# Board1a.net
KiCad netlist of a schematic drawn in EAGLE
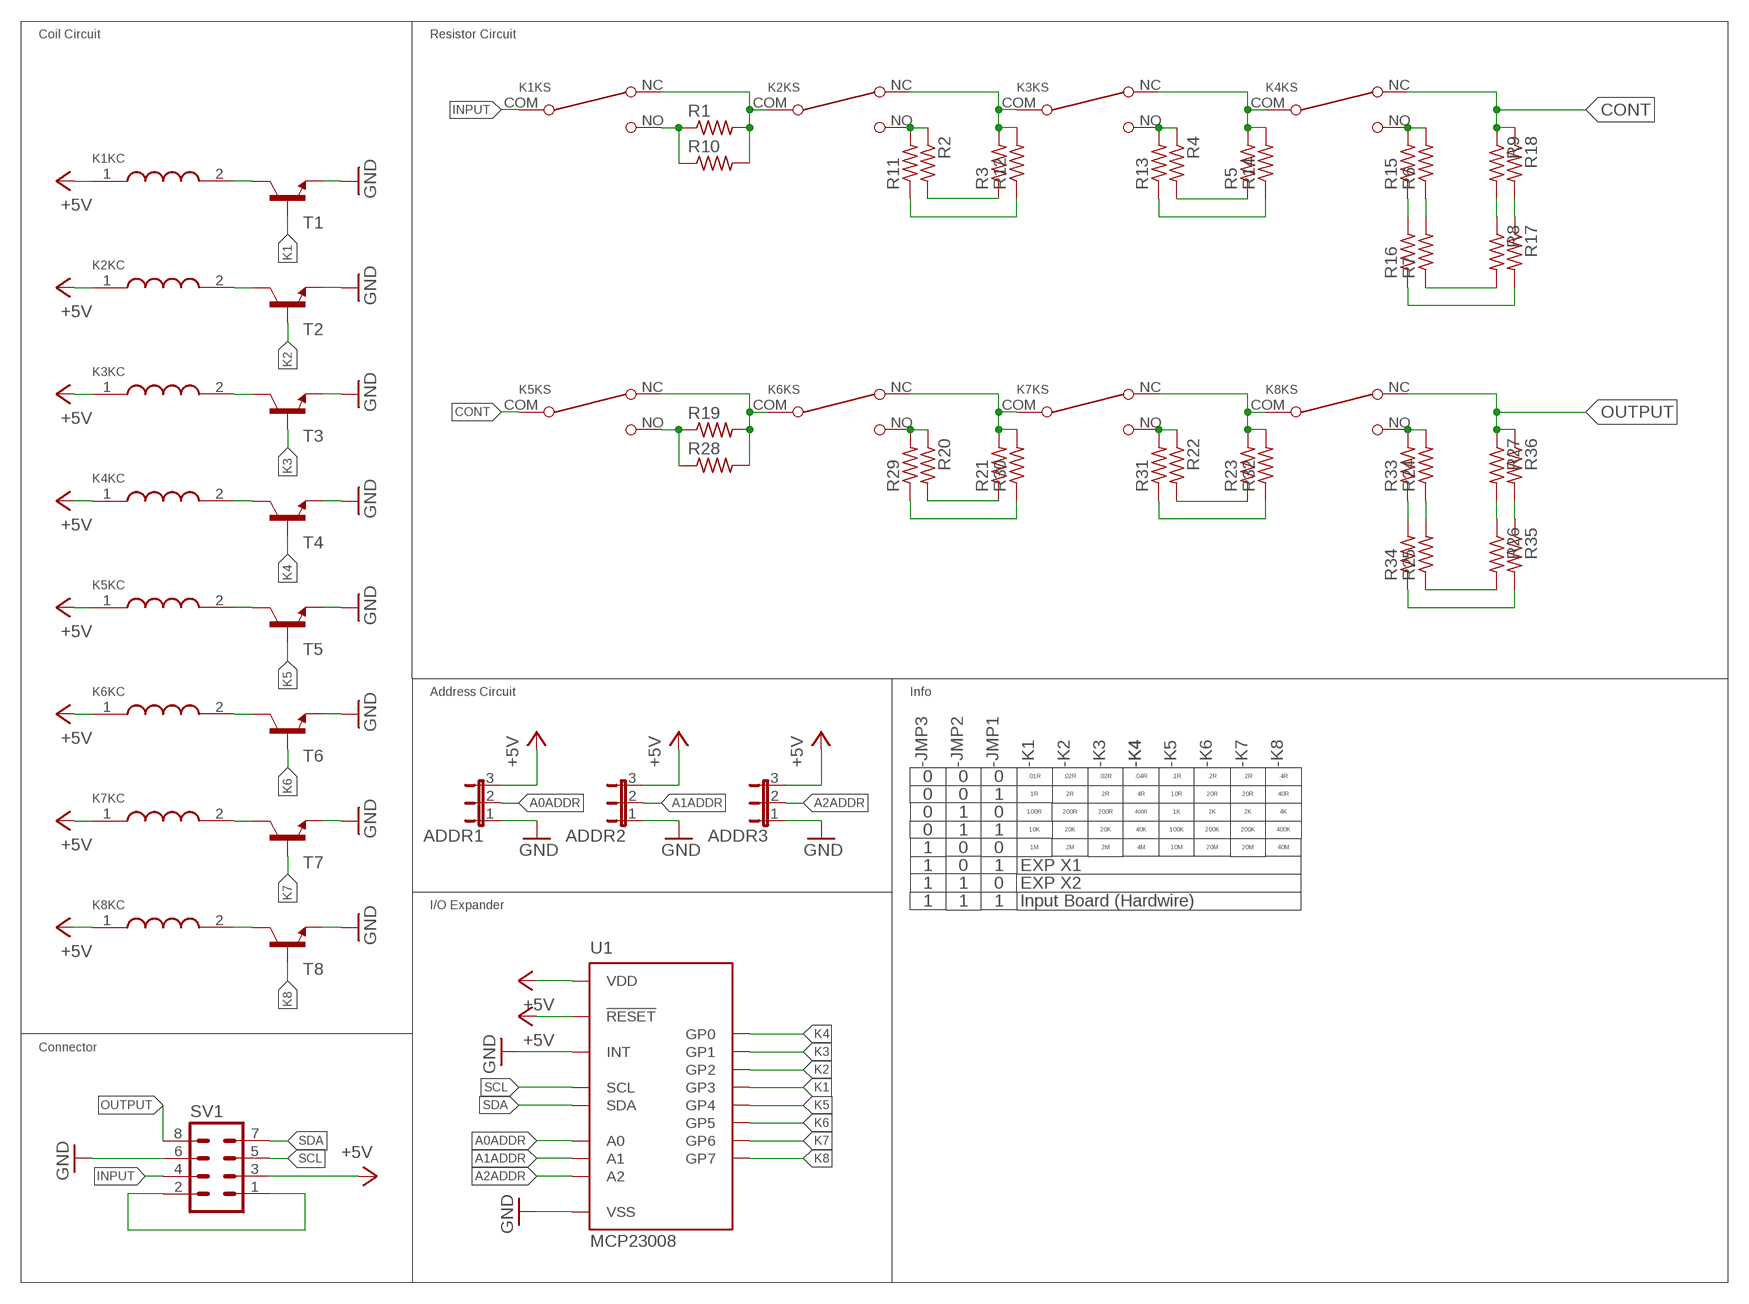
[diagram p0: schematic, sheet 1]

(export (version "E")
  (design (tool "Eeschema 10.0.6"))
  (components
    (comp (ref "ADDR1")
      (value "JP2E")
      (footprint "eagle-import:JP2")
      (libsource (lib "eagle-import") (part "JP2E"))
    )
    (comp (ref "ADDR2")
      (value "JP2E")
      (footprint "eagle-import:JP2")
      (libsource (lib "eagle-import") (part "JP2E"))
    )
    (comp (ref "ADDR3")
      (value "JP2E")
      (footprint "eagle-import:JP2")
      (libsource (lib "eagle-import") (part "JP2E"))
    )
    (comp (ref "K1")
      (value "G5LE-1-VD DC12")
      (footprint "eagle-import:G5LE")
      (libsource (lib "eagle-import") (part "G5LE"))
    )
    (comp (ref "K2")
      (value "G5LE")
      (footprint "eagle-import:G5LE")
      (libsource (lib "eagle-import") (part "G5LE"))
    )
    (comp (ref "K3")
      (value "G5LE")
      (footprint "eagle-import:G5LE")
      (libsource (lib "eagle-import") (part "G5LE"))
    )
    (comp (ref "K4")
      (value "G5LE")
      (footprint "eagle-import:G5LE")
      (libsource (lib "eagle-import") (part "G5LE"))
    )
    (comp (ref "K5")
      (value "G5LE-1-VD DC12")
      (footprint "eagle-import:G5LE")
      (libsource (lib "eagle-import") (part "G5LE"))
    )
    (comp (ref "K6")
      (value "G5LE")
      (footprint "eagle-import:G5LE")
      (libsource (lib "eagle-import") (part "G5LE"))
    )
    (comp (ref "K7")
      (value "G5LE")
      (footprint "eagle-import:G5LE")
      (libsource (lib "eagle-import") (part "G5LE"))
    )
    (comp (ref "K8")
      (value "G5LE")
      (footprint "eagle-import:G5LE")
      (libsource (lib "eagle-import") (part "G5LE"))
    )
    (comp (ref "R1")
      (value "R-US_0613/5V")
      (footprint "eagle-import:P0613V")
      (libsource (lib "eagle-import") (part "R-US_0613/5V"))
    )
    (comp (ref "R2")
      (value "R-US_0613/5V")
      (footprint "eagle-import:P0613V")
      (libsource (lib "eagle-import") (part "R-US_0613/5V"))
    )
    (comp (ref "R3")
      (value "R-US_0613/5V")
      (footprint "eagle-import:P0613V")
      (libsource (lib "eagle-import") (part "R-US_0613/5V"))
    )
    (comp (ref "R4")
      (value "R-US_0613/5V")
      (footprint "eagle-import:P0613V")
      (libsource (lib "eagle-import") (part "R-US_0613/5V"))
    )
    (comp (ref "R5")
      (value "R-US_0613/5V")
      (footprint "eagle-import:P0613V")
      (libsource (lib "eagle-import") (part "R-US_0613/5V"))
    )
    (comp (ref "R6")
      (value "R-US_0613/5V")
      (footprint "eagle-import:P0613V")
      (libsource (lib "eagle-import") (part "R-US_0613/5V"))
    )
    (comp (ref "R7")
      (value "R-US_0613/5V")
      (footprint "eagle-import:P0613V")
      (libsource (lib "eagle-import") (part "R-US_0613/5V"))
    )
    (comp (ref "R8")
      (value "R-US_0613/5V")
      (footprint "eagle-import:P0613V")
      (libsource (lib "eagle-import") (part "R-US_0613/5V"))
    )
    (comp (ref "R9")
      (value "R-US_0613/5V")
      (footprint "eagle-import:P0613V")
      (libsource (lib "eagle-import") (part "R-US_0613/5V"))
    )
    (comp (ref "R10")
      (value "R-US_M1206")
      (footprint "eagle-import:M1206")
      (libsource (lib "eagle-import") (part "R-US_M1206"))
    )
    (comp (ref "R11")
      (value "R-US_M1206")
      (footprint "eagle-import:M1206")
      (libsource (lib "eagle-import") (part "R-US_M1206"))
    )
    (comp (ref "R12")
      (value "R-US_M1206")
      (footprint "eagle-import:M1206")
      (libsource (lib "eagle-import") (part "R-US_M1206"))
    )
    (comp (ref "R13")
      (value "R-US_M1206")
      (footprint "eagle-import:M1206")
      (libsource (lib "eagle-import") (part "R-US_M1206"))
    )
    (comp (ref "R14")
      (value "R-US_M1206")
      (footprint "eagle-import:M1206")
      (libsource (lib "eagle-import") (part "R-US_M1206"))
    )
    (comp (ref "R15")
      (value "R-US_M1206")
      (footprint "eagle-import:M1206")
      (libsource (lib "eagle-import") (part "R-US_M1206"))
    )
    (comp (ref "R16")
      (value "R-US_M1206")
      (footprint "eagle-import:M1206")
      (libsource (lib "eagle-import") (part "R-US_M1206"))
    )
    (comp (ref "R17")
      (value "R-US_M1206")
      (footprint "eagle-import:M1206")
      (libsource (lib "eagle-import") (part "R-US_M1206"))
    )
    (comp (ref "R18")
      (value "R-US_M1206")
      (footprint "eagle-import:M1206")
      (libsource (lib "eagle-import") (part "R-US_M1206"))
    )
    (comp (ref "R19")
      (value "R-US_0613/5V")
      (footprint "eagle-import:P0613V")
      (libsource (lib "eagle-import") (part "R-US_0613/5V"))
    )
    (comp (ref "R20")
      (value "R-US_0613/5V")
      (footprint "eagle-import:P0613V")
      (libsource (lib "eagle-import") (part "R-US_0613/5V"))
    )
    (comp (ref "R21")
      (value "R-US_0613/5V")
      (footprint "eagle-import:P0613V")
      (libsource (lib "eagle-import") (part "R-US_0613/5V"))
    )
    (comp (ref "R22")
      (value "R-US_0613/5V")
      (footprint "eagle-import:P0613V")
      (libsource (lib "eagle-import") (part "R-US_0613/5V"))
    )
    (comp (ref "R23")
      (value "R-US_0613/5V")
      (footprint "eagle-import:P0613V")
      (libsource (lib "eagle-import") (part "R-US_0613/5V"))
    )
    (comp (ref "R24")
      (value "R-US_0613/5V")
      (footprint "eagle-import:P0613V")
      (libsource (lib "eagle-import") (part "R-US_0613/5V"))
    )
    (comp (ref "R25")
      (value "R-US_0613/5V")
      (footprint "eagle-import:P0613V")
      (libsource (lib "eagle-import") (part "R-US_0613/5V"))
    )
    (comp (ref "R26")
      (value "R-US_0613/5V")
      (footprint "eagle-import:P0613V")
      (libsource (lib "eagle-import") (part "R-US_0613/5V"))
    )
    (comp (ref "R27")
      (value "R-US_0613/5V")
      (footprint "eagle-import:P0613V")
      (libsource (lib "eagle-import") (part "R-US_0613/5V"))
    )
    (comp (ref "R28")
      (value "R-US_M1206")
      (footprint "eagle-import:M1206")
      (libsource (lib "eagle-import") (part "R-US_M1206"))
    )
    (comp (ref "R29")
      (value "R-US_M1206")
      (footprint "eagle-import:M1206")
      (libsource (lib "eagle-import") (part "R-US_M1206"))
    )
    (comp (ref "R30")
      (value "R-US_M1206")
      (footprint "eagle-import:M1206")
      (libsource (lib "eagle-import") (part "R-US_M1206"))
    )
    (comp (ref "R31")
      (value "R-US_M1206")
      (footprint "eagle-import:M1206")
      (libsource (lib "eagle-import") (part "R-US_M1206"))
    )
    (comp (ref "R32")
      (value "R-US_M1206")
      (footprint "eagle-import:M1206")
      (libsource (lib "eagle-import") (part "R-US_M1206"))
    )
    (comp (ref "R33")
      (value "R-US_M1206")
      (footprint "eagle-import:M1206")
      (libsource (lib "eagle-import") (part "R-US_M1206"))
    )
    (comp (ref "R34")
      (value "R-US_M1206")
      (footprint "eagle-import:M1206")
      (libsource (lib "eagle-import") (part "R-US_M1206"))
    )
    (comp (ref "R35")
      (value "R-US_M1206")
      (footprint "eagle-import:M1206")
      (libsource (lib "eagle-import") (part "R-US_M1206"))
    )
    (comp (ref "R36")
      (value "R-US_M1206")
      (footprint "eagle-import:M1206")
      (libsource (lib "eagle-import") (part "R-US_M1206"))
    )
    (comp (ref "SV1")
      (value "MA04-2")
      (footprint "eagle-import:MA04-2")
      (libsource (lib "eagle-import") (part "MA04-2"))
    )
    (comp (ref "T1")
      (value "MMUN2211LT1-NPN-SC59-BEC")
      (footprint "eagle-import:SC59-BEC")
      (libsource (lib "eagle-import") (part "-NPN-SC59-BECMMUN2211LT1"))
    )
    (comp (ref "T2")
      (value "MMUN2211LT1-NPN-SC59-BEC")
      (footprint "eagle-import:SC59-BEC")
      (libsource (lib "eagle-import") (part "-NPN-SC59-BECMMUN2211LT1"))
    )
    (comp (ref "T3")
      (value "MMUN2211LT1-NPN-SC59-BEC")
      (footprint "eagle-import:SC59-BEC")
      (libsource (lib "eagle-import") (part "-NPN-SC59-BECMMUN2211LT1"))
    )
    (comp (ref "T4")
      (value "MMUN2211LT1-NPN-SC59-BEC")
      (footprint "eagle-import:SC59-BEC")
      (libsource (lib "eagle-import") (part "-NPN-SC59-BECMMUN2211LT1"))
    )
    (comp (ref "T5")
      (value "MMUN2211LT1-NPN-SC59-BEC")
      (footprint "eagle-import:SC59-BEC")
      (libsource (lib "eagle-import") (part "-NPN-SC59-BECMMUN2211LT1"))
    )
    (comp (ref "T6")
      (value "MMUN2211LT1-NPN-SC59-BEC")
      (footprint "eagle-import:SC59-BEC")
      (libsource (lib "eagle-import") (part "-NPN-SC59-BECMMUN2211LT1"))
    )
    (comp (ref "T7")
      (value "MMUN2211LT1-NPN-SC59-BEC")
      (footprint "eagle-import:SC59-BEC")
      (libsource (lib "eagle-import") (part "-NPN-SC59-BECMMUN2211LT1"))
    )
    (comp (ref "T8")
      (value "MMUN2211LT1-NPN-SC59-BEC")
      (footprint "eagle-import:SC59-BEC")
      (libsource (lib "eagle-import") (part "-NPN-SC59-BECMMUN2211LT1"))
    )
    (comp (ref "U1")
      (value "MCP23008")
      (footprint "eagle-import:SOIC")
      (libsource (lib "eagle-import") (part "MCP23008"))
    )
  )
  (nets
    (net (code "1") (name "+5V") (class "Default")
      (node (ref "ADDR1") (pin "3") (pinfunction "3_3") (pintype "passive"))
      (node (ref "ADDR2") (pin "3") (pinfunction "3_3") (pintype "passive"))
      (node (ref "ADDR3") (pin "3") (pinfunction "3_3") (pintype "passive"))
      (node (ref "K1") (pin "1") (pinfunction "COILA_1") (pintype "bidirectional"))
      (node (ref "K2") (pin "1") (pinfunction "COILA_1") (pintype "bidirectional"))
      (node (ref "K3") (pin "1") (pinfunction "COILA_1") (pintype "bidirectional"))
      (node (ref "K4") (pin "1") (pinfunction "COILA_1") (pintype "bidirectional"))
      (node (ref "K5") (pin "1") (pinfunction "COILA_1") (pintype "bidirectional"))
      (node (ref "K6") (pin "1") (pinfunction "COILA_1") (pintype "bidirectional"))
      (node (ref "K7") (pin "1") (pinfunction "COILA_1") (pintype "bidirectional"))
      (node (ref "K8") (pin "1") (pinfunction "COILA_1") (pintype "bidirectional"))
      (node (ref "SV1") (pin "3") (pinfunction "3_3") (pintype "passive"))
      (node (ref "U1") (pin "P$18") (pinfunction "VDD_P$18") (pintype "power_in"))
      (node (ref "U1") (pin "P$6") (pinfunction "~{RESET}_P$6") (pintype "input"))
    )
    (net (code "2") (name "A0ADDR") (class "Default")
      (node (ref "ADDR1") (pin "2") (pinfunction "2_2") (pintype "passive"))
      (node (ref "U1") (pin "P$5") (pinfunction "A0_P$5") (pintype "input"))
    )
    (net (code "3") (name "A1ADDR") (class "Default")
      (node (ref "ADDR2") (pin "2") (pinfunction "2_2") (pintype "passive"))
      (node (ref "U1") (pin "P$4") (pinfunction "A1_P$4") (pintype "input"))
    )
    (net (code "4") (name "A2ADDR") (class "Default")
      (node (ref "ADDR3") (pin "2") (pinfunction "2_2") (pintype "passive"))
      (node (ref "U1") (pin "P$3") (pinfunction "A2_P$3") (pintype "input"))
    )
    (net (code "5") (name "CONT") (class "Default")
      (node (ref "K4") (pin "NC") (pinfunction "P$NC_NC") (pintype "bidirectional"))
      (node (ref "K5") (pin "COM") (pinfunction "P$COM_COM") (pintype "bidirectional"))
      (node (ref "R18") (pin "1") (pinfunction "1_1") (pintype "passive"))
      (node (ref "R9") (pin "1") (pinfunction "1_1") (pintype "passive"))
    )
    (net (code "6") (name "GND") (class "Default")
      (node (ref "ADDR1") (pin "1") (pinfunction "1_1") (pintype "passive"))
      (node (ref "ADDR2") (pin "1") (pinfunction "1_1") (pintype "passive"))
      (node (ref "ADDR3") (pin "1") (pinfunction "1_1") (pintype "passive"))
      (node (ref "SV1") (pin "6") (pinfunction "6_6") (pintype "passive"))
      (node (ref "T1") (pin "E") (pinfunction "E_E") (pintype "passive"))
      (node (ref "T2") (pin "E") (pinfunction "E_E") (pintype "passive"))
      (node (ref "T3") (pin "E") (pinfunction "E_E") (pintype "passive"))
      (node (ref "T4") (pin "E") (pinfunction "E_E") (pintype "passive"))
      (node (ref "T5") (pin "E") (pinfunction "E_E") (pintype "passive"))
      (node (ref "T6") (pin "E") (pinfunction "E_E") (pintype "passive"))
      (node (ref "T7") (pin "E") (pinfunction "E_E") (pintype "passive"))
      (node (ref "T8") (pin "E") (pinfunction "E_E") (pintype "passive"))
      (node (ref "U1") (pin "P$8") (pinfunction "INT_P$8") (pintype "output"))
      (node (ref "U1") (pin "P$9") (pinfunction "VSS_P$9") (pintype "power_in"))
    )
    (net (code "7") (name "INPUT") (class "Default")
      (node (ref "K1") (pin "COM") (pinfunction "P$COM_COM") (pintype "bidirectional"))
      (node (ref "SV1") (pin "4") (pinfunction "4_4") (pintype "passive"))
    )
    (net (code "8") (name "K1") (class "Default")
      (node (ref "T1") (pin "B") (pinfunction "B_B") (pintype "passive"))
      (node (ref "U1") (pin "P$13") (pinfunction "GP3_P$13") (pintype "bidirectional"))
    )
    (net (code "9") (name "K2") (class "Default")
      (node (ref "T2") (pin "B") (pinfunction "B_B") (pintype "passive"))
      (node (ref "U1") (pin "P$12") (pinfunction "GP2_P$12") (pintype "bidirectional"))
    )
    (net (code "10") (name "K3") (class "Default")
      (node (ref "T3") (pin "B") (pinfunction "B_B") (pintype "passive"))
      (node (ref "U1") (pin "P$11") (pinfunction "GP1_P$11") (pintype "bidirectional"))
    )
    (net (code "11") (name "K4") (class "Default")
      (node (ref "T4") (pin "B") (pinfunction "B_B") (pintype "passive"))
      (node (ref "U1") (pin "P$10") (pinfunction "GP0_P$10") (pintype "bidirectional"))
    )
    (net (code "12") (name "K5") (class "Default")
      (node (ref "T5") (pin "B") (pinfunction "B_B") (pintype "passive"))
      (node (ref "U1") (pin "P$14") (pinfunction "GP4_P$14") (pintype "bidirectional"))
    )
    (net (code "13") (name "K6") (class "Default")
      (node (ref "T6") (pin "B") (pinfunction "B_B") (pintype "passive"))
      (node (ref "U1") (pin "P$15") (pinfunction "GP5_P$15") (pintype "bidirectional"))
    )
    (net (code "14") (name "K7") (class "Default")
      (node (ref "T7") (pin "B") (pinfunction "B_B") (pintype "passive"))
      (node (ref "U1") (pin "P$16") (pinfunction "GP6_P$16") (pintype "bidirectional"))
    )
    (net (code "15") (name "K8") (class "Default")
      (node (ref "T8") (pin "B") (pinfunction "B_B") (pintype "passive"))
      (node (ref "U1") (pin "P$17") (pinfunction "GP7_P$17") (pintype "bidirectional"))
    )
    (net (code "16") (name "Net-(K1A-COILB)") (class "Default")
      (node (ref "K1") (pin "2") (pinfunction "COILB_2") (pintype "bidirectional"))
      (node (ref "T1") (pin "C") (pinfunction "C_C") (pintype "passive"))
    )
    (net (code "17") (name "Net-(K1B-P$NC)") (class "Default")
      (node (ref "K1") (pin "NC") (pinfunction "P$NC_NC") (pintype "bidirectional"))
      (node (ref "K2") (pin "COM") (pinfunction "P$COM_COM") (pintype "bidirectional"))
      (node (ref "R1") (pin "2") (pinfunction "2_2") (pintype "passive"))
      (node (ref "R10") (pin "2") (pinfunction "2_2") (pintype "passive"))
    )
    (net (code "18") (name "Net-(K1B-P$NO)") (class "Default")
      (node (ref "K1") (pin "NO") (pinfunction "P$NO_NO") (pintype "bidirectional"))
      (node (ref "R1") (pin "1") (pinfunction "1_1") (pintype "passive"))
      (node (ref "R10") (pin "1") (pinfunction "1_1") (pintype "passive"))
    )
    (net (code "19") (name "Net-(K2A-COILB)") (class "Default")
      (node (ref "K2") (pin "2") (pinfunction "COILB_2") (pintype "bidirectional"))
      (node (ref "T2") (pin "C") (pinfunction "C_C") (pintype "passive"))
    )
    (net (code "20") (name "Net-(K2B-P$NC)") (class "Default")
      (node (ref "K2") (pin "NC") (pinfunction "P$NC_NC") (pintype "bidirectional"))
      (node (ref "K3") (pin "COM") (pinfunction "P$COM_COM") (pintype "bidirectional"))
      (node (ref "R12") (pin "2") (pinfunction "2_2") (pintype "passive"))
      (node (ref "R3") (pin "2") (pinfunction "2_2") (pintype "passive"))
    )
    (net (code "21") (name "Net-(K2B-P$NO)") (class "Default")
      (node (ref "K2") (pin "NO") (pinfunction "P$NO_NO") (pintype "bidirectional"))
      (node (ref "R11") (pin "2") (pinfunction "2_2") (pintype "passive"))
      (node (ref "R2") (pin "1") (pinfunction "1_1") (pintype "passive"))
    )
    (net (code "22") (name "Net-(K3A-COILB)") (class "Default")
      (node (ref "K3") (pin "2") (pinfunction "COILB_2") (pintype "bidirectional"))
      (node (ref "T3") (pin "C") (pinfunction "C_C") (pintype "passive"))
    )
    (net (code "23") (name "Net-(K3B-P$NC)") (class "Default")
      (node (ref "K3") (pin "NC") (pinfunction "P$NC_NC") (pintype "bidirectional"))
      (node (ref "K4") (pin "COM") (pinfunction "P$COM_COM") (pintype "bidirectional"))
      (node (ref "R14") (pin "2") (pinfunction "2_2") (pintype "passive"))
      (node (ref "R5") (pin "2") (pinfunction "2_2") (pintype "passive"))
    )
    (net (code "24") (name "Net-(K3B-P$NO)") (class "Default")
      (node (ref "K3") (pin "NO") (pinfunction "P$NO_NO") (pintype "bidirectional"))
      (node (ref "R13") (pin "2") (pinfunction "2_2") (pintype "passive"))
      (node (ref "R4") (pin "1") (pinfunction "1_1") (pintype "passive"))
    )
    (net (code "25") (name "Net-(K4A-COILB)") (class "Default")
      (node (ref "K4") (pin "2") (pinfunction "COILB_2") (pintype "bidirectional"))
      (node (ref "T4") (pin "C") (pinfunction "C_C") (pintype "passive"))
    )
    (net (code "26") (name "Net-(K4B-P$NO)") (class "Default")
      (node (ref "K4") (pin "NO") (pinfunction "P$NO_NO") (pintype "bidirectional"))
      (node (ref "R15") (pin "2") (pinfunction "2_2") (pintype "passive"))
      (node (ref "R6") (pin "2") (pinfunction "2_2") (pintype "passive"))
    )
    (net (code "27") (name "Net-(K5A-COILB)") (class "Default")
      (node (ref "K5") (pin "2") (pinfunction "COILB_2") (pintype "bidirectional"))
      (node (ref "T5") (pin "C") (pinfunction "C_C") (pintype "passive"))
    )
    (net (code "28") (name "Net-(K5B-P$NC)") (class "Default")
      (node (ref "K5") (pin "NC") (pinfunction "P$NC_NC") (pintype "bidirectional"))
      (node (ref "K6") (pin "COM") (pinfunction "P$COM_COM") (pintype "bidirectional"))
      (node (ref "R19") (pin "2") (pinfunction "2_2") (pintype "passive"))
      (node (ref "R28") (pin "2") (pinfunction "2_2") (pintype "passive"))
    )
    (net (code "29") (name "Net-(K5B-P$NO)") (class "Default")
      (node (ref "K5") (pin "NO") (pinfunction "P$NO_NO") (pintype "bidirectional"))
      (node (ref "R19") (pin "1") (pinfunction "1_1") (pintype "passive"))
      (node (ref "R28") (pin "1") (pinfunction "1_1") (pintype "passive"))
    )
    (net (code "30") (name "Net-(K6A-COILB)") (class "Default")
      (node (ref "K6") (pin "2") (pinfunction "COILB_2") (pintype "bidirectional"))
      (node (ref "T6") (pin "C") (pinfunction "C_C") (pintype "passive"))
    )
    (net (code "31") (name "Net-(K6B-P$NC)") (class "Default")
      (node (ref "K6") (pin "NC") (pinfunction "P$NC_NC") (pintype "bidirectional"))
      (node (ref "K7") (pin "COM") (pinfunction "P$COM_COM") (pintype "bidirectional"))
      (node (ref "R21") (pin "2") (pinfunction "2_2") (pintype "passive"))
      (node (ref "R30") (pin "2") (pinfunction "2_2") (pintype "passive"))
    )
    (net (code "32") (name "Net-(K6B-P$NO)") (class "Default")
      (node (ref "K6") (pin "NO") (pinfunction "P$NO_NO") (pintype "bidirectional"))
      (node (ref "R20") (pin "1") (pinfunction "1_1") (pintype "passive"))
      (node (ref "R29") (pin "2") (pinfunction "2_2") (pintype "passive"))
    )
    (net (code "33") (name "Net-(K7A-COILB)") (class "Default")
      (node (ref "K7") (pin "2") (pinfunction "COILB_2") (pintype "bidirectional"))
      (node (ref "T7") (pin "C") (pinfunction "C_C") (pintype "passive"))
    )
    (net (code "34") (name "Net-(K7B-P$NC)") (class "Default")
      (node (ref "K7") (pin "NC") (pinfunction "P$NC_NC") (pintype "bidirectional"))
      (node (ref "K8") (pin "COM") (pinfunction "P$COM_COM") (pintype "bidirectional"))
      (node (ref "R23") (pin "2") (pinfunction "2_2") (pintype "passive"))
      (node (ref "R32") (pin "2") (pinfunction "2_2") (pintype "passive"))
    )
    (net (code "35") (name "Net-(K7B-P$NO)") (class "Default")
      (node (ref "K7") (pin "NO") (pinfunction "P$NO_NO") (pintype "bidirectional"))
      (node (ref "R22") (pin "1") (pinfunction "1_1") (pintype "passive"))
      (node (ref "R31") (pin "2") (pinfunction "2_2") (pintype "passive"))
    )
    (net (code "36") (name "Net-(K8A-COILB)") (class "Default")
      (node (ref "K8") (pin "2") (pinfunction "COILB_2") (pintype "bidirectional"))
      (node (ref "T8") (pin "C") (pinfunction "C_C") (pintype "passive"))
    )
    (net (code "37") (name "Net-(K8B-P$NO)") (class "Default")
      (node (ref "K8") (pin "NO") (pinfunction "P$NO_NO") (pintype "bidirectional"))
      (node (ref "R24") (pin "2") (pinfunction "2_2") (pintype "passive"))
      (node (ref "R33") (pin "2") (pinfunction "2_2") (pintype "passive"))
    )
    (net (code "38") (name "Net-(R2-Pad2)") (class "Default")
      (node (ref "R2") (pin "2") (pinfunction "2_2") (pintype "passive"))
      (node (ref "R3") (pin "1") (pinfunction "1_1") (pintype "passive"))
    )
    (net (code "39") (name "Net-(R4-Pad2)") (class "Default")
      (node (ref "R4") (pin "2") (pinfunction "2_2") (pintype "passive"))
      (node (ref "R5") (pin "1") (pinfunction "1_1") (pintype "passive"))
    )
    (net (code "40") (name "Net-(R6-Pad1)") (class "Default")
      (node (ref "R6") (pin "1") (pinfunction "1_1") (pintype "passive"))
      (node (ref "R7") (pin "2") (pinfunction "2_2") (pintype "passive"))
    )
    (net (code "41") (name "Net-(R7-Pad1)") (class "Default")
      (node (ref "R7") (pin "1") (pinfunction "1_1") (pintype "passive"))
      (node (ref "R8") (pin "2") (pinfunction "2_2") (pintype "passive"))
    )
    (net (code "42") (name "Net-(R8-Pad1)") (class "Default")
      (node (ref "R8") (pin "1") (pinfunction "1_1") (pintype "passive"))
      (node (ref "R9") (pin "2") (pinfunction "2_2") (pintype "passive"))
    )
    (net (code "43") (name "Net-(R11-Pad1)") (class "Default")
      (node (ref "R11") (pin "1") (pinfunction "1_1") (pintype "passive"))
      (node (ref "R12") (pin "1") (pinfunction "1_1") (pintype "passive"))
    )
    (net (code "44") (name "Net-(R13-Pad1)") (class "Default")
      (node (ref "R13") (pin "1") (pinfunction "1_1") (pintype "passive"))
      (node (ref "R14") (pin "1") (pinfunction "1_1") (pintype "passive"))
    )
    (net (code "45") (name "Net-(R15-Pad1)") (class "Default")
      (node (ref "R15") (pin "1") (pinfunction "1_1") (pintype "passive"))
      (node (ref "R16") (pin "2") (pinfunction "2_2") (pintype "passive"))
    )
    (net (code "46") (name "Net-(R16-Pad1)") (class "Default")
      (node (ref "R16") (pin "1") (pinfunction "1_1") (pintype "passive"))
      (node (ref "R17") (pin "2") (pinfunction "2_2") (pintype "passive"))
    )
    (net (code "47") (name "Net-(R17-Pad1)") (class "Default")
      (node (ref "R17") (pin "1") (pinfunction "1_1") (pintype "passive"))
      (node (ref "R18") (pin "2") (pinfunction "2_2") (pintype "passive"))
    )
    (net (code "48") (name "Net-(R20-Pad2)") (class "Default")
      (node (ref "R20") (pin "2") (pinfunction "2_2") (pintype "passive"))
      (node (ref "R21") (pin "1") (pinfunction "1_1") (pintype "passive"))
    )
    (net (code "49") (name "Net-(R22-Pad2)") (class "Default")
      (node (ref "R22") (pin "2") (pinfunction "2_2") (pintype "passive"))
      (node (ref "R23") (pin "1") (pinfunction "1_1") (pintype "passive"))
    )
    (net (code "50") (name "Net-(R24-Pad1)") (class "Default")
      (node (ref "R24") (pin "1") (pinfunction "1_1") (pintype "passive"))
      (node (ref "R25") (pin "2") (pinfunction "2_2") (pintype "passive"))
    )
    (net (code "51") (name "Net-(R25-Pad1)") (class "Default")
      (node (ref "R25") (pin "1") (pinfunction "1_1") (pintype "passive"))
      (node (ref "R26") (pin "2") (pinfunction "2_2") (pintype "passive"))
    )
    (net (code "52") (name "Net-(R26-Pad1)") (class "Default")
      (node (ref "R26") (pin "1") (pinfunction "1_1") (pintype "passive"))
      (node (ref "R27") (pin "2") (pinfunction "2_2") (pintype "passive"))
    )
    (net (code "53") (name "Net-(R29-Pad1)") (class "Default")
      (node (ref "R29") (pin "1") (pinfunction "1_1") (pintype "passive"))
      (node (ref "R30") (pin "1") (pinfunction "1_1") (pintype "passive"))
    )
    (net (code "54") (name "Net-(R31-Pad1)") (class "Default")
      (node (ref "R31") (pin "1") (pinfunction "1_1") (pintype "passive"))
      (node (ref "R32") (pin "1") (pinfunction "1_1") (pintype "passive"))
    )
    (net (code "55") (name "Net-(R33-Pad1)") (class "Default")
      (node (ref "R33") (pin "1") (pinfunction "1_1") (pintype "passive"))
      (node (ref "R34") (pin "2") (pinfunction "2_2") (pintype "passive"))
    )
    (net (code "56") (name "Net-(R34-Pad1)") (class "Default")
      (node (ref "R34") (pin "1") (pinfunction "1_1") (pintype "passive"))
      (node (ref "R35") (pin "2") (pinfunction "2_2") (pintype "passive"))
    )
    (net (code "57") (name "Net-(R35-Pad1)") (class "Default")
      (node (ref "R35") (pin "1") (pinfunction "1_1") (pintype "passive"))
      (node (ref "R36") (pin "2") (pinfunction "2_2") (pintype "passive"))
    )
    (net (code "58") (name "Net-(SV1-Pad1)") (class "Default")
      (node (ref "SV1") (pin "1") (pinfunction "1_1") (pintype "passive"))
      (node (ref "SV1") (pin "2") (pinfunction "2_2") (pintype "passive"))
    )
    (net (code "59") (name "OUTPUT") (class "Default")
      (node (ref "K8") (pin "NC") (pinfunction "P$NC_NC") (pintype "bidirectional"))
      (node (ref "R27") (pin "1") (pinfunction "1_1") (pintype "passive"))
      (node (ref "R36") (pin "1") (pinfunction "1_1") (pintype "passive"))
      (node (ref "SV1") (pin "8") (pinfunction "8_8") (pintype "passive"))
    )
    (net (code "60") (name "SCL") (class "Default")
      (node (ref "SV1") (pin "5") (pinfunction "5_5") (pintype "passive"))
      (node (ref "U1") (pin "P$1") (pinfunction "SCL_P$1") (pintype "input"))
    )
    (net (code "61") (name "SDA") (class "Default")
      (node (ref "SV1") (pin "7") (pinfunction "7_7") (pintype "passive"))
      (node (ref "U1") (pin "P$2") (pinfunction "SDA_P$2") (pintype "bidirectional"))
    )
  )
)
